# droneHAT.net
KiCad netlist of a schematic drawn in EAGLE
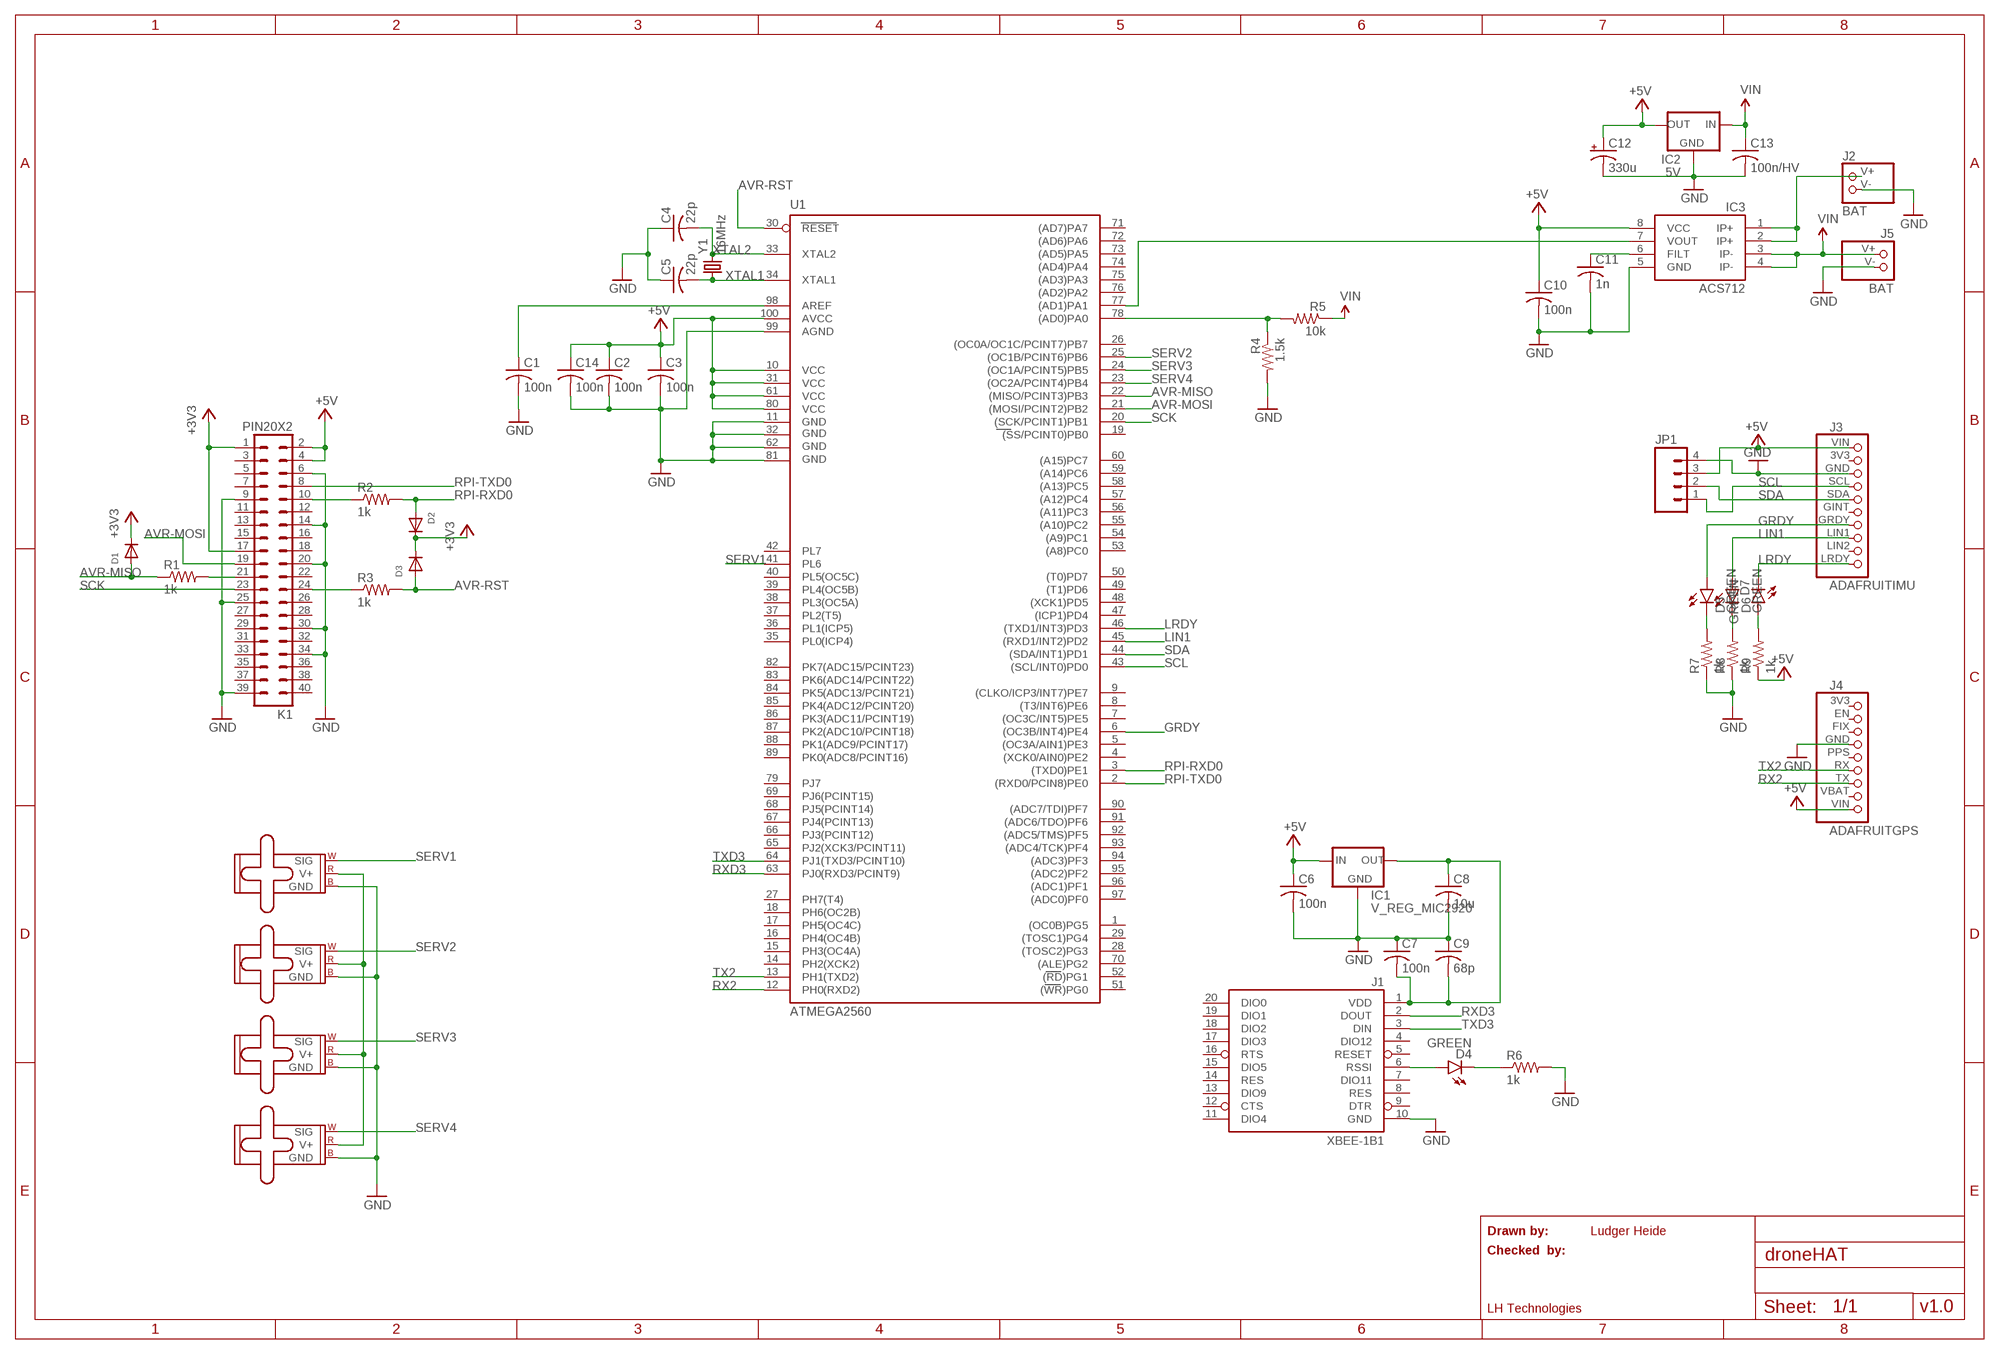
[diagram p0: schematic, sheet 1]

(export (version "E")
  (design (tool "Eeschema 10.0.6"))
  (components
    (comp (ref "C1")
      (value "100n")
      (footprint "eagle-import:C1206")
      (libsource (lib "eagle-import") (part "C-USC1206"))
    )
    (comp (ref "C2")
      (value "100n")
      (footprint "eagle-import:C1206")
      (libsource (lib "eagle-import") (part "C-USC1206"))
    )
    (comp (ref "C3")
      (value "100n")
      (footprint "eagle-import:C1206")
      (libsource (lib "eagle-import") (part "C-USC1206"))
    )
    (comp (ref "C4")
      (value "22p")
      (footprint "eagle-import:C1206")
      (libsource (lib "eagle-import") (part "C-USC1206"))
    )
    (comp (ref "C5")
      (value "22p")
      (footprint "eagle-import:C1206")
      (libsource (lib "eagle-import") (part "C-USC1206"))
    )
    (comp (ref "C6")
      (value "100n")
      (footprint "eagle-import:C1206")
      (libsource (lib "eagle-import") (part "C-USC1206"))
    )
    (comp (ref "C7")
      (value "100n")
      (footprint "eagle-import:C1206")
      (libsource (lib "eagle-import") (part "C-USC1206"))
    )
    (comp (ref "C8")
      (value "10u")
      (footprint "eagle-import:C1206")
      (libsource (lib "eagle-import") (part "C-USC1206"))
    )
    (comp (ref "C9")
      (value "68p")
      (footprint "eagle-import:C1206")
      (libsource (lib "eagle-import") (part "C-USC1206"))
    )
    (comp (ref "C10")
      (value "100n")
      (footprint "eagle-import:C1206")
      (libsource (lib "eagle-import") (part "C-USC1206"))
    )
    (comp (ref "C11")
      (value "1n")
      (footprint "eagle-import:C1206")
      (libsource (lib "eagle-import") (part "C-USC1206"))
    )
    (comp (ref "C12")
      (value "330u")
      (footprint "eagle-import:CPOL-RADIAL-100UF-25V")
      (libsource (lib "eagle-import") (part "CAP_POLPTH1"))
    )
    (comp (ref "C13")
      (value "100n/HV")
      (footprint "eagle-import:C1206")
      (libsource (lib "eagle-import") (part "C-USC1206"))
    )
    (comp (ref "C14")
      (value "100n")
      (footprint "eagle-import:C1206")
      (libsource (lib "eagle-import") (part "C-USC1206"))
    )
    (comp (ref "D1")
      (value "DIODEDO-1N4148")
      (footprint "eagle-import:DO-1N4148")
      (libsource (lib "eagle-import") (part "DIODEDO-1N4148"))
    )
    (comp (ref "D2")
      (value "DIODEDO-1N4148")
      (footprint "eagle-import:DO-1N4148")
      (libsource (lib "eagle-import") (part "DIODEDO-1N4148"))
    )
    (comp (ref "D3")
      (value "DIODEDO-1N4148")
      (footprint "eagle-import:DO-1N4148")
      (libsource (lib "eagle-import") (part "DIODEDO-1N4148"))
    )
    (comp (ref "D4")
      (value "GREEN")
      (footprint "eagle-import:LED-1206")
      (libsource (lib "eagle-import") (part "LED-GREENLARGE"))
    )
    (comp (ref "D5")
      (value "GREEN")
      (footprint "eagle-import:LED-1206")
      (libsource (lib "eagle-import") (part "LED-GREENLARGE"))
    )
    (comp (ref "D6")
      (value "GREEN")
      (footprint "eagle-import:LED-1206")
      (libsource (lib "eagle-import") (part "LED-GREENLARGE"))
    )
    (comp (ref "D7")
      (value "GREEN")
      (footprint "eagle-import:LED-1206")
      (libsource (lib "eagle-import") (part "LED-GREENLARGE"))
    )
    (comp (ref "IC1")
      (value "V_REG_MIC2920")
      (footprint "eagle-import:SOT223")
      (libsource (lib "eagle-import") (part "V_REG_MIC2920"))
    )
    (comp (ref "IC2")
      (value "5V")
      (footprint "eagle-import:TSRN1")
      (libsource (lib "eagle-import") (part "V_REG_78XX"))
    )
    (comp (ref "IC3")
      (value "ACS712")
      (footprint "eagle-import:SO08")
      (libsource (lib "eagle-import") (part "ACS712"))
    )
    (comp (ref "J1")
      (value "XBEE-1B1")
      (footprint "eagle-import:XBEE-1")
      (libsource (lib "eagle-import") (part "XBEE-1B1"))
    )
    (comp (ref "J2")
      (value "BAT")
      (footprint "eagle-import:BAT_HDR")
      (libsource (lib "eagle-import") (part "BAT"))
    )
    (comp (ref "J3")
      (value "ADAFRUITIMU")
      (footprint "eagle-import:ADAIMU")
      (libsource (lib "eagle-import") (part "ADAFRUITIMU"))
    )
    (comp (ref "J4")
      (value "ADAFRUITGPS")
      (footprint "eagle-import:ADAGPS")
      (libsource (lib "eagle-import") (part "ADAFRUITGPS"))
    )
    (comp (ref "J5")
      (value "BAT")
      (footprint "eagle-import:BAT_HDR")
      (libsource (lib "eagle-import") (part "BAT"))
    )
    (comp (ref "JP1")
      (value "M04PTH")
      (footprint "eagle-import:1X04")
      (libsource (lib "eagle-import") (part "M04PTH"))
    )
    (comp (ref "K1")
      (value "PIN20X2")
      (footprint "eagle-import:PIN_20X2")
      (libsource (lib "eagle-import") (part "PIN20X2"))
    )
    (comp (ref "M1")
      (value "SMALL_SERVO")
      (footprint "eagle-import:1X03")
      (libsource (lib "eagle-import") (part "SMALL_SERVO"))
    )
    (comp (ref "M2")
      (value "SMALL_SERVO")
      (footprint "eagle-import:1X03")
      (libsource (lib "eagle-import") (part "SMALL_SERVO"))
    )
    (comp (ref "M3")
      (value "SMALL_SERVO")
      (footprint "eagle-import:1X03")
      (libsource (lib "eagle-import") (part "SMALL_SERVO"))
    )
    (comp (ref "M4")
      (value "SMALL_SERVO")
      (footprint "eagle-import:1X03")
      (libsource (lib "eagle-import") (part "SMALL_SERVO"))
    )
    (comp (ref "R1")
      (value "1k")
      (footprint "eagle-import:M1206")
      (libsource (lib "eagle-import") (part "R-US_M1206"))
    )
    (comp (ref "R2")
      (value "1k")
      (footprint "eagle-import:M1206")
      (libsource (lib "eagle-import") (part "R-US_M1206"))
    )
    (comp (ref "R3")
      (value "1k")
      (footprint "eagle-import:M1206")
      (libsource (lib "eagle-import") (part "R-US_M1206"))
    )
    (comp (ref "R4")
      (value "1.5k")
      (footprint "eagle-import:M1206")
      (libsource (lib "eagle-import") (part "R-US_M1206"))
    )
    (comp (ref "R5")
      (value "10k")
      (footprint "eagle-import:M1206")
      (libsource (lib "eagle-import") (part "R-US_M1206"))
    )
    (comp (ref "R6")
      (value "1k")
      (footprint "eagle-import:M1206")
      (libsource (lib "eagle-import") (part "R-US_M1206"))
    )
    (comp (ref "R7")
      (value "1k")
      (footprint "eagle-import:M1206")
      (libsource (lib "eagle-import") (part "R-US_M1206"))
    )
    (comp (ref "R8")
      (value "1k")
      (footprint "eagle-import:M1206")
      (libsource (lib "eagle-import") (part "R-US_M1206"))
    )
    (comp (ref "R9")
      (value "1k")
      (footprint "eagle-import:M1206")
      (libsource (lib "eagle-import") (part "R-US_M1206"))
    )
    (comp (ref "U1")
      (value "ATMEGA2560")
      (footprint "eagle-import:TQFP100-LONG")
      (libsource (lib "eagle-import") (part "ATMEGA2560"))
    )
    (comp (ref "Y1")
      (value "16MHz")
      (footprint "eagle-import:HC49US")
      (libsource (lib "eagle-import") (part "CRYSTALHC49US"))
    )
  )
  (nets
    (net (code "1") (name "+3V3") (class "Default")
      (node (ref "D1") (pin "C") (pinfunction "C_C") (pintype "passive"))
      (node (ref "D2") (pin "C") (pinfunction "C_C") (pintype "passive"))
      (node (ref "D3") (pin "C") (pinfunction "C_C") (pintype "passive"))
      (node (ref "K1") (pin "1") (pinfunction "1_1") (pintype "passive"))
      (node (ref "K1") (pin "17") (pinfunction "17_17") (pintype "passive"))
    )
    (net (code "2") (name "+5V") (class "Default")
      (node (ref "C10") (pin "1") (pinfunction "1_1") (pintype "passive"))
      (node (ref "C12") (pin "1") (pinfunction "+_1") (pintype "passive"))
      (node (ref "C14") (pin "1") (pinfunction "1_1") (pintype "passive"))
      (node (ref "C2") (pin "1") (pinfunction "1_1") (pintype "passive"))
      (node (ref "C3") (pin "1") (pinfunction "1_1") (pintype "passive"))
      (node (ref "C6") (pin "1") (pinfunction "1_1") (pintype "passive"))
      (node (ref "IC1") (pin "1") (pinfunction "IN_1") (pintype "input"))
      (node (ref "IC2") (pin "3") (pinfunction "OUT_3") (pintype "output"))
      (node (ref "IC3") (pin "8") (pinfunction "VCC_8") (pintype "bidirectional"))
      (node (ref "J3") (pin "VIN") (pinfunction "1_VIN") (pintype "passive"))
      (node (ref "J4") (pin "VIN") (pinfunction "9_VIN") (pintype "passive"))
      (node (ref "JP1") (pin "3") (pinfunction "3_3") (pintype "passive"))
      (node (ref "K1") (pin "2") (pinfunction "2_2") (pintype "passive"))
      (node (ref "K1") (pin "4") (pinfunction "4_4") (pintype "passive"))
      (node (ref "R9") (pin "1") (pinfunction "1_1") (pintype "passive"))
      (node (ref "U1") (pin "10") (pinfunction "VCC_10") (pintype "power_in"))
      (node (ref "U1") (pin "100") (pinfunction "AVCC_100") (pintype "power_in"))
      (node (ref "U1") (pin "31") (pinfunction "VCC1_31") (pintype "power_in"))
      (node (ref "U1") (pin "61") (pinfunction "VCC2_61") (pintype "power_in"))
      (node (ref "U1") (pin "80") (pinfunction "VCC3_80") (pintype "power_in"))
    )
    (net (code "3") (name "/AVR-MISO") (class "Default")
      (node (ref "D1") (pin "A") (pinfunction "A_A") (pintype "passive"))
      (node (ref "R1") (pin "1") (pinfunction "1_1") (pintype "passive"))
      (node (ref "U1") (pin "22") (pinfunction "(MISO/PCINT3)PB3_22") (pintype "bidirectional"))
    )
    (net (code "4") (name "/AVR-MOSI") (class "Default")
      (node (ref "K1") (pin "19") (pinfunction "19_19") (pintype "passive"))
      (node (ref "U1") (pin "21") (pinfunction "(MOSI/PCINT2)PB2_21") (pintype "bidirectional"))
    )
    (net (code "5") (name "/AVR-RST") (class "Default")
      (node (ref "D3") (pin "A") (pinfunction "A_A") (pintype "passive"))
      (node (ref "R3") (pin "2") (pinfunction "2_2") (pintype "passive"))
      (node (ref "U1") (pin "30") (pinfunction "RESET_30") (pintype "input"))
    )
    (net (code "6") (name "/GRDY") (class "Default")
      (node (ref "D5") (pin "A") (pinfunction "A_A") (pintype "passive"))
      (node (ref "J3") (pin "GRDY") (pinfunction "7_GRDY") (pintype "passive"))
      (node (ref "U1") (pin "6") (pinfunction "(OC3B/INT4)PE4_6") (pintype "bidirectional"))
    )
    (net (code "7") (name "/LIN1") (class "Default")
      (node (ref "D6") (pin "A") (pinfunction "A_A") (pintype "passive"))
      (node (ref "J3") (pin "LIN1") (pinfunction "8_LIN1") (pintype "passive"))
      (node (ref "U1") (pin "45") (pinfunction "(RXD1/INT2)PD2_45") (pintype "bidirectional"))
    )
    (net (code "8") (name "/LRDY") (class "Default")
      (node (ref "D7") (pin "C") (pinfunction "C_C") (pintype "passive"))
      (node (ref "J3") (pin "LRDY") (pinfunction "10_LRDY") (pintype "passive"))
      (node (ref "U1") (pin "46") (pinfunction "(TXD1/INT3)PD3_46") (pintype "bidirectional"))
    )
    (net (code "9") (name "/RPI-RXD0") (class "Default")
      (node (ref "D2") (pin "A") (pinfunction "A_A") (pintype "passive"))
      (node (ref "R2") (pin "2") (pinfunction "2_2") (pintype "passive"))
      (node (ref "U1") (pin "3") (pinfunction "(TXD0)PE1_3") (pintype "bidirectional"))
    )
    (net (code "10") (name "/RPI-TXD0") (class "Default")
      (node (ref "K1") (pin "8") (pinfunction "8_8") (pintype "passive"))
      (node (ref "U1") (pin "2") (pinfunction "(RXD0/PCIN8)PE0_2") (pintype "bidirectional"))
    )
    (net (code "11") (name "/RX2") (class "Default")
      (node (ref "J4") (pin "TX") (pinfunction "7_TX") (pintype "passive"))
      (node (ref "U1") (pin "12") (pinfunction "PH0(RXD2)_12") (pintype "bidirectional"))
    )
    (net (code "12") (name "/RXD3") (class "Default")
      (node (ref "J1") (pin "2") (pinfunction "DOUT_2") (pintype "output"))
      (node (ref "U1") (pin "63") (pinfunction "PJ0(RXD3/PCINT9)_63") (pintype "bidirectional"))
    )
    (net (code "13") (name "/SCK") (class "Default")
      (node (ref "K1") (pin "23") (pinfunction "23_23") (pintype "passive"))
      (node (ref "U1") (pin "20") (pinfunction "(SCK/PCINT1)PB1_20") (pintype "bidirectional"))
    )
    (net (code "14") (name "/SCL") (class "Default")
      (node (ref "J3") (pin "SCL") (pinfunction "4_SCL") (pintype "passive"))
      (node (ref "JP1") (pin "1") (pinfunction "1_1") (pintype "passive"))
      (node (ref "U1") (pin "43") (pinfunction "(SCL/INT0)PD0_43") (pintype "bidirectional"))
    )
    (net (code "15") (name "/SDA") (class "Default")
      (node (ref "J3") (pin "SDA") (pinfunction "5_SDA") (pintype "passive"))
      (node (ref "JP1") (pin "2") (pinfunction "2_2") (pintype "passive"))
      (node (ref "U1") (pin "44") (pinfunction "(SDA/INT1)PD1_44") (pintype "bidirectional"))
    )
    (net (code "16") (name "/SERV1") (class "Default")
      (node (ref "M1") (pin "1") (pinfunction "SIG_1") (pintype "bidirectional"))
      (node (ref "U1") (pin "41") (pinfunction "PL6_41") (pintype "bidirectional"))
    )
    (net (code "17") (name "/SERV2") (class "Default")
      (node (ref "M2") (pin "1") (pinfunction "SIG_1") (pintype "bidirectional"))
      (node (ref "U1") (pin "25") (pinfunction "(OC1B/PCINT6)PB6_25") (pintype "bidirectional"))
    )
    (net (code "18") (name "/SERV3") (class "Default")
      (node (ref "M3") (pin "1") (pinfunction "SIG_1") (pintype "bidirectional"))
      (node (ref "U1") (pin "24") (pinfunction "(OC1A/PCINT5)PB5_24") (pintype "bidirectional"))
    )
    (net (code "19") (name "/SERV4") (class "Default")
      (node (ref "M4") (pin "1") (pinfunction "SIG_1") (pintype "bidirectional"))
      (node (ref "U1") (pin "23") (pinfunction "(OC2A/PCINT4)PB4_23") (pintype "bidirectional"))
    )
    (net (code "20") (name "/TX2") (class "Default")
      (node (ref "J4") (pin "RX") (pinfunction "6_RX") (pintype "passive"))
      (node (ref "U1") (pin "13") (pinfunction "PH1(TXD2)_13") (pintype "bidirectional"))
    )
    (net (code "21") (name "/TXD3") (class "Default")
      (node (ref "J1") (pin "3") (pinfunction "DIN_3") (pintype "input"))
      (node (ref "U1") (pin "64") (pinfunction "PJ1(TXD3/PCINT10)_64") (pintype "bidirectional"))
    )
    (net (code "22") (name "/XTAL1") (class "Default")
      (node (ref "C5") (pin "2") (pinfunction "2_2") (pintype "passive"))
      (node (ref "U1") (pin "34") (pinfunction "XTAL1_34") (pintype "input"))
      (node (ref "Y1") (pin "1") (pinfunction "1_1") (pintype "passive"))
    )
    (net (code "23") (name "/XTAL2") (class "Default")
      (node (ref "C4") (pin "2") (pinfunction "2_2") (pintype "passive"))
      (node (ref "U1") (pin "33") (pinfunction "XTAL2_33") (pintype "output"))
      (node (ref "Y1") (pin "2") (pinfunction "2_2") (pintype "passive"))
    )
    (net (code "24") (name "GND") (class "Default")
      (node (ref "C1") (pin "2") (pinfunction "2_2") (pintype "passive"))
      (node (ref "C10") (pin "2") (pinfunction "2_2") (pintype "passive"))
      (node (ref "C11") (pin "2") (pinfunction "2_2") (pintype "passive"))
      (node (ref "C12") (pin "2") (pinfunction "-_2") (pintype "passive"))
      (node (ref "C13") (pin "2") (pinfunction "2_2") (pintype "passive"))
      (node (ref "C14") (pin "2") (pinfunction "2_2") (pintype "passive"))
      (node (ref "C2") (pin "2") (pinfunction "2_2") (pintype "passive"))
      (node (ref "C3") (pin "2") (pinfunction "2_2") (pintype "passive"))
      (node (ref "C4") (pin "1") (pinfunction "1_1") (pintype "passive"))
      (node (ref "C5") (pin "1") (pinfunction "1_1") (pintype "passive"))
      (node (ref "C6") (pin "2") (pinfunction "2_2") (pintype "passive"))
      (node (ref "C7") (pin "1") (pinfunction "1_1") (pintype "passive"))
      (node (ref "C8") (pin "2") (pinfunction "2_2") (pintype "passive"))
      (node (ref "C9") (pin "1") (pinfunction "1_1") (pintype "passive"))
      (node (ref "IC1") (pin "2") (pinfunction "GND_2") (pintype "input"))
      (node (ref "IC2") (pin "2") (pinfunction "GND_2") (pintype "input"))
      (node (ref "IC3") (pin "5") (pinfunction "GND_5") (pintype "bidirectional"))
      (node (ref "J1") (pin "10") (pinfunction "GND_10") (pintype "power_in"))
      (node (ref "J2") (pin "V-") (pinfunction "V-_V-") (pintype "passive"))
      (node (ref "J3") (pin "GND") (pinfunction "3_GND") (pintype "passive"))
      (node (ref "J4") (pin "GND") (pinfunction "4_GND") (pintype "passive"))
      (node (ref "J5") (pin "V-") (pinfunction "V-_V-") (pintype "passive"))
      (node (ref "JP1") (pin "4") (pinfunction "4_4") (pintype "passive"))
      (node (ref "K1") (pin "14") (pinfunction "14_14") (pintype "passive"))
      (node (ref "K1") (pin "20") (pinfunction "20_20") (pintype "passive"))
      (node (ref "K1") (pin "25") (pinfunction "25_25") (pintype "passive"))
      (node (ref "K1") (pin "30") (pinfunction "30_30") (pintype "passive"))
      (node (ref "K1") (pin "34") (pinfunction "34_34") (pintype "passive"))
      (node (ref "K1") (pin "39") (pinfunction "39_39") (pintype "passive"))
      (node (ref "K1") (pin "6") (pinfunction "6_6") (pintype "passive"))
      (node (ref "K1") (pin "9") (pinfunction "9_9") (pintype "passive"))
      (node (ref "M1") (pin "3") (pinfunction "GND_3") (pintype "bidirectional"))
      (node (ref "M2") (pin "3") (pinfunction "GND_3") (pintype "bidirectional"))
      (node (ref "M3") (pin "3") (pinfunction "GND_3") (pintype "bidirectional"))
      (node (ref "M4") (pin "3") (pinfunction "GND_3") (pintype "bidirectional"))
      (node (ref "R4") (pin "2") (pinfunction "2_2") (pintype "passive"))
      (node (ref "R6") (pin "2") (pinfunction "2_2") (pintype "passive"))
      (node (ref "R7") (pin "1") (pinfunction "1_1") (pintype "passive"))
      (node (ref "R8") (pin "1") (pinfunction "1_1") (pintype "passive"))
      (node (ref "U1") (pin "11") (pinfunction "GND_11") (pintype "power_in"))
      (node (ref "U1") (pin "32") (pinfunction "GND1_32") (pintype "power_in"))
      (node (ref "U1") (pin "62") (pinfunction "GND2_62") (pintype "power_in"))
      (node (ref "U1") (pin "81") (pinfunction "GND3_81") (pintype "power_in"))
      (node (ref "U1") (pin "99") (pinfunction "AGND_99") (pintype "power_in"))
    )
    (net (code "25") (name "Net-(D4-PadC)") (class "Default")
      (node (ref "D4") (pin "C") (pinfunction "C_C") (pintype "passive"))
      (node (ref "R6") (pin "1") (pinfunction "1_1") (pintype "passive"))
    )
    (net (code "26") (name "Net-(D5-PadC)") (class "Default")
      (node (ref "D5") (pin "C") (pinfunction "C_C") (pintype "passive"))
      (node (ref "R7") (pin "2") (pinfunction "2_2") (pintype "passive"))
    )
    (net (code "27") (name "Net-(D6-PadC)") (class "Default")
      (node (ref "D6") (pin "C") (pinfunction "C_C") (pintype "passive"))
      (node (ref "R8") (pin "2") (pinfunction "2_2") (pintype "passive"))
    )
    (net (code "28") (name "Net-(D7-PadA)") (class "Default")
      (node (ref "D7") (pin "A") (pinfunction "A_A") (pintype "passive"))
      (node (ref "R9") (pin "2") (pinfunction "2_2") (pintype "passive"))
    )
    (net (code "29") (name "Net-(IC1-OUT)") (class "Default")
      (node (ref "C7") (pin "2") (pinfunction "2_2") (pintype "passive"))
      (node (ref "C8") (pin "1") (pinfunction "1_1") (pintype "passive"))
      (node (ref "C9") (pin "2") (pinfunction "2_2") (pintype "passive"))
      (node (ref "IC1") (pin "3") (pinfunction "OUT_3") (pintype "output"))
      (node (ref "J1") (pin "1") (pinfunction "VDD_1") (pintype "power_in"))
    )
    (net (code "30") (name "Net-(IC3-FILT)") (class "Default")
      (node (ref "C11") (pin "1") (pinfunction "1_1") (pintype "passive"))
      (node (ref "IC3") (pin "6") (pinfunction "FILT_6") (pintype "bidirectional"))
    )
    (net (code "31") (name "Net-(IC3-IP+-Pad1)") (class "Default")
      (node (ref "IC3") (pin "1") (pinfunction "IP+_1") (pintype "bidirectional"))
      (node (ref "IC3") (pin "2") (pinfunction "IP+_2") (pintype "bidirectional"))
      (node (ref "J2") (pin "V+") (pinfunction "V+_V+") (pintype "passive"))
    )
    (net (code "32") (name "Net-(IC3-VOUT)") (class "Default")
      (node (ref "IC3") (pin "7") (pinfunction "VOUT_7") (pintype "bidirectional"))
      (node (ref "U1") (pin "77") (pinfunction "(AD1)PA1_77") (pintype "bidirectional"))
    )
    (net (code "33") (name "Net-(J1-RSSI)") (class "Default")
      (node (ref "D4") (pin "A") (pinfunction "A_A") (pintype "passive"))
      (node (ref "J1") (pin "6") (pinfunction "RSSI_6") (pintype "bidirectional"))
    )
    (net (code "34") (name "Net-(K1-Pad10)") (class "Default")
      (node (ref "K1") (pin "10") (pinfunction "10_10") (pintype "passive"))
      (node (ref "R2") (pin "1") (pinfunction "1_1") (pintype "passive"))
    )
    (net (code "35") (name "Net-(K1-Pad21)") (class "Default")
      (node (ref "K1") (pin "21") (pinfunction "21_21") (pintype "passive"))
      (node (ref "R1") (pin "2") (pinfunction "2_2") (pintype "passive"))
    )
    (net (code "36") (name "Net-(K1-Pad24)") (class "Default")
      (node (ref "K1") (pin "24") (pinfunction "24_24") (pintype "passive"))
      (node (ref "R3") (pin "1") (pinfunction "1_1") (pintype "passive"))
    )
    (net (code "37") (name "Net-(M1-V+)") (class "Default")
      (node (ref "M1") (pin "2") (pinfunction "V+_2") (pintype "bidirectional"))
      (node (ref "M2") (pin "2") (pinfunction "V+_2") (pintype "bidirectional"))
      (node (ref "M3") (pin "2") (pinfunction "V+_2") (pintype "bidirectional"))
      (node (ref "M4") (pin "2") (pinfunction "V+_2") (pintype "bidirectional"))
    )
    (net (code "38") (name "Net-(U1-(AD0)PA0)") (class "Default")
      (node (ref "R4") (pin "1") (pinfunction "1_1") (pintype "passive"))
      (node (ref "R5") (pin "2") (pinfunction "2_2") (pintype "passive"))
      (node (ref "U1") (pin "78") (pinfunction "(AD0)PA0_78") (pintype "bidirectional"))
    )
    (net (code "39") (name "Net-(U1-AREF)") (class "Default")
      (node (ref "C1") (pin "1") (pinfunction "1_1") (pintype "passive"))
      (node (ref "U1") (pin "98") (pinfunction "AREF_98") (pintype "bidirectional"))
    )
    (net (code "40") (name "VIN") (class "Default")
      (node (ref "C13") (pin "1") (pinfunction "1_1") (pintype "passive"))
      (node (ref "IC2") (pin "1") (pinfunction "IN_1") (pintype "input"))
      (node (ref "IC3") (pin "3") (pinfunction "IP-_3") (pintype "bidirectional"))
      (node (ref "IC3") (pin "4") (pinfunction "IP-_4") (pintype "bidirectional"))
      (node (ref "J5") (pin "V+") (pinfunction "V+_V+") (pintype "passive"))
      (node (ref "R5") (pin "1") (pinfunction "1_1") (pintype "passive"))
    )
    (net (code "41") (name "unconnected-(J1-CTS-Pad12)") (class "Default")
      (node (ref "J1") (pin "12") (pinfunction "CTS_12") (pintype "output"))
    )
    (net (code "42") (name "unconnected-(J1-DIO0-Pad20)") (class "Default")
      (node (ref "J1") (pin "20") (pinfunction "DIO0_20") (pintype "bidirectional"))
    )
    (net (code "43") (name "unconnected-(J1-DIO1-Pad19)") (class "Default")
      (node (ref "J1") (pin "19") (pinfunction "DIO1_19") (pintype "bidirectional"))
    )
    (net (code "44") (name "unconnected-(J1-DIO2-Pad18)") (class "Default")
      (node (ref "J1") (pin "18") (pinfunction "DIO2_18") (pintype "bidirectional"))
    )
    (net (code "45") (name "unconnected-(J1-DIO3-Pad17)") (class "Default")
      (node (ref "J1") (pin "17") (pinfunction "DIO3_17") (pintype "bidirectional"))
    )
    (net (code "46") (name "unconnected-(J1-DIO4-Pad11)") (class "Default")
      (node (ref "J1") (pin "11") (pinfunction "DIO4_11") (pintype "bidirectional"))
    )
    (net (code "47") (name "unconnected-(J1-DIO5-Pad15)") (class "Default")
      (node (ref "J1") (pin "15") (pinfunction "DIO5_15") (pintype "bidirectional"))
    )
    (net (code "48") (name "unconnected-(J1-DIO9-Pad13)") (class "Default")
      (node (ref "J1") (pin "13") (pinfunction "DIO9_13") (pintype "bidirectional"))
    )
    (net (code "49") (name "unconnected-(J1-DIO11-Pad7)") (class "Default")
      (node (ref "J1") (pin "7") (pinfunction "DIO11_7") (pintype "bidirectional"))
    )
    (net (code "50") (name "unconnected-(J1-DIO12-Pad4)") (class "Default")
      (node (ref "J1") (pin "4") (pinfunction "DIO12_4") (pintype "bidirectional"))
    )
    (net (code "51") (name "unconnected-(J1-DTR-Pad9)") (class "Default")
      (node (ref "J1") (pin "9") (pinfunction "DTR_9") (pintype "bidirectional"))
    )
    (net (code "52") (name "unconnected-(J1-RES-Pad8)") (class "Default")
      (node (ref "J1") (pin "8") (pinfunction "RES_8") (pintype "bidirectional"))
    )
    (net (code "53") (name "unconnected-(J1-RES-Pad14)") (class "Default")
      (node (ref "J1") (pin "14") (pinfunction "RES_14") (pintype "bidirectional"))
    )
    (net (code "54") (name "unconnected-(J1-RESET-Pad5)") (class "Default")
      (node (ref "J1") (pin "5") (pinfunction "RESET_5") (pintype "input"))
    )
    (net (code "55") (name "unconnected-(J1-RTS-Pad16)") (class "Default")
      (node (ref "J1") (pin "16") (pinfunction "RTS_16") (pintype "input"))
    )
    (net (code "56") (name "unconnected-(J3-2-Pad3V3)") (class "Default")
      (node (ref "J3") (pin "3V3") (pinfunction "2_3V3") (pintype "passive"))
    )
    (net (code "57") (name "unconnected-(J3-6-PadGINT)") (class "Default")
      (node (ref "J3") (pin "GINT") (pinfunction "6_GINT") (pintype "passive"))
    )
    (net (code "58") (name "unconnected-(J3-9-PadLIN2)") (class "Default")
      (node (ref "J3") (pin "LIN2") (pinfunction "9_LIN2") (pintype "passive"))
    )
    (net (code "59") (name "unconnected-(J4-1-Pad3V3)") (class "Default")
      (node (ref "J4") (pin "3V3") (pinfunction "1_3V3") (pintype "passive"))
    )
    (net (code "60") (name "unconnected-(J4-2-PadEN)") (class "Default")
      (node (ref "J4") (pin "EN") (pinfunction "2_EN") (pintype "passive"))
    )
    (net (code "61") (name "unconnected-(J4-3-PadFIX)") (class "Default")
      (node (ref "J4") (pin "FIX") (pinfunction "3_FIX") (pintype "passive"))
    )
    (net (code "62") (name "unconnected-(J4-5-PadPPS)") (class "Default")
      (node (ref "J4") (pin "PPS") (pinfunction "5_PPS") (pintype "passive"))
    )
    (net (code "63") (name "unconnected-(J4-8-PadVBAT)") (class "Default")
      (node (ref "J4") (pin "VBAT") (pinfunction "8_VBAT") (pintype "passive"))
    )
    (net (code "64") (name "unconnected-(K1-Pad3)") (class "Default")
      (node (ref "K1") (pin "3") (pinfunction "3_3") (pintype "passive"))
    )
    (net (code "65") (name "unconnected-(K1-Pad5)") (class "Default")
      (node (ref "K1") (pin "5") (pinfunction "5_5") (pintype "passive"))
    )
    (net (code "66") (name "unconnected-(K1-Pad7)") (class "Default")
      (node (ref "K1") (pin "7") (pinfunction "7_7") (pintype "passive"))
    )
    (net (code "67") (name "unconnected-(K1-Pad11)") (class "Default")
      (node (ref "K1") (pin "11") (pinfunction "11_11") (pintype "passive"))
    )
    (net (code "68") (name "unconnected-(K1-Pad12)") (class "Default")
      (node (ref "K1") (pin "12") (pinfunction "12_12") (pintype "passive"))
    )
    (net (code "69") (name "unconnected-(K1-Pad13)") (class "Default")
      (node (ref "K1") (pin "13") (pinfunction "13_13") (pintype "passive"))
    )
    (net (code "70") (name "unconnected-(K1-Pad15)") (class "Default")
      (node (ref "K1") (pin "15") (pinfunction "15_15") (pintype "passive"))
    )
    (net (code "71") (name "unconnected-(K1-Pad16)") (class "Default")
      (node (ref "K1") (pin "16") (pinfunction "16_16") (pintype "passive"))
    )
    (net (code "72") (name "unconnected-(K1-Pad18)") (class "Default")
      (node (ref "K1") (pin "18") (pinfunction "18_18") (pintype "passive"))
    )
    (net (code "73") (name "unconnected-(K1-Pad22)") (class "Default")
      (node (ref "K1") (pin "22") (pinfunction "22_22") (pintype "passive"))
    )
    (net (code "74") (name "unconnected-(K1-Pad26)") (class "Default")
      (node (ref "K1") (pin "26") (pinfunction "26_26") (pintype "passive"))
    )
    (net (code "75") (name "unconnected-(K1-Pad27)") (class "Default")
      (node (ref "K1") (pin "27") (pinfunction "27_27") (pintype "passive"))
    )
    (net (code "76") (name "unconnected-(K1-Pad28)") (class "Default")
      (node (ref "K1") (pin "28") (pinfunction "28_28") (pintype "passive"))
    )
    (net (code "77") (name "unconnected-(K1-Pad29)") (class "Default")
      (node (ref "K1") (pin "29") (pinfunction "29_29") (pintype "passive"))
    )
    (net (code "78") (name "unconnected-(K1-Pad31)") (class "Default")
      (node (ref "K1") (pin "31") (pinfunction "31_31") (pintype "passive"))
    )
    (net (code "79") (name "unconnected-(K1-Pad32)") (class "Default")
      (node (ref "K1") (pin "32") (pinfunction "32_32") (pintype "passive"))
    )
    (net (code "80") (name "unconnected-(K1-Pad33)") (class "Default")
      (node (ref "K1") (pin "33") (pinfunction "33_33") (pintype "passive"))
    )
    (net (code "81") (name "unconnected-(K1-Pad35)") (class "Default")
      (node (ref "K1") (pin "35") (pinfunction "35_35") (pintype "passive"))
    )
    (net (code "82") (name "unconnected-(K1-Pad36)") (class "Default")
      (node (ref "K1") (pin "36") (pinfunction "36_36") (pintype "passive"))
    )
    (net (code "83") (name "unconnected-(K1-Pad37)") (class "Default")
      (node (ref "K1") (pin "37") (pinfunction "37_37") (pintype "passive"))
    )
    (net (code "84") (name "unconnected-(K1-Pad38)") (class "Default")
      (node (ref "K1") (pin "38") (pinfunction "38_38") (pintype "passive"))
    )
    (net (code "85") (name "unconnected-(K1-Pad40)") (class "Default")
      (node (ref "K1") (pin "40") (pinfunction "40_40") (pintype "passive"))
    )
    (net (code "86") (name "unconnected-(U1-(A8)PC0-Pad53)") (class "Default")
      (node (ref "U1") (pin "53") (pinfunction "(A8)PC0_53") (pintype "bidirectional"))
    )
    (net (code "87") (name "unconnected-(U1-(A9)PC1-Pad54)") (class "Default")
      (node (ref "U1") (pin "54") (pinfunction "(A9)PC1_54") (pintype "bidirectional"))
    )
    (net (code "88") (name "unconnected-(U1-(A10)PC2-Pad55)") (class "Default")
      (node (ref "U1") (pin "55") (pinfunction "(A10)PC2_55") (pintype "bidirectional"))
    )
    (net (code "89") (name "unconnected-(U1-(A11)PC3-Pad56)") (class "Default")
      (node (ref "U1") (pin "56") (pinfunction "(A11)PC3_56") (pintype "bidirectional"))
    )
    (net (code "90") (name "unconnected-(U1-(A12)PC4-Pad57)") (class "Default")
      (node (ref "U1") (pin "57") (pinfunction "(A12)PC4_57") (pintype "bidirectional"))
    )
    (net (code "91") (name "unconnected-(U1-(A13)PC5-Pad58)") (class "Default")
      (node (ref "U1") (pin "58") (pinfunction "(A13)PC5_58") (pintype "bidirectional"))
    )
    (net (code "92") (name "unconnected-(U1-(A14)PC6-Pad59)") (class "Default")
      (node (ref "U1") (pin "59") (pinfunction "(A14)PC6_59") (pintype "bidirectional"))
    )
    (net (code "93") (name "unconnected-(U1-(A15)PC7-Pad60)") (class "Default")
      (node (ref "U1") (pin "60") (pinfunction "(A15)PC7_60") (pintype "bidirectional"))
    )
    (net (code "94") (name "unconnected-(U1-(AD2)PA2-Pad76)") (class "Default")
      (node (ref "U1") (pin "76") (pinfunction "(AD2)PA2_76") (pintype "bidirectional"))
    )
    (net (code "95") (name "unconnected-(U1-(AD3)PA3-Pad75)") (class "Default")
      (node (ref "U1") (pin "75") (pinfunction "(AD3)PA3_75") (pintype "bidirectional"))
    )
    (net (code "96") (name "unconnected-(U1-(AD4)PA4-Pad74)") (class "Default")
      (node (ref "U1") (pin "74") (pinfunction "(AD4)PA4_74") (pintype "bidirectional"))
    )
    (net (code "97") (name "unconnected-(U1-(AD5)PA5-Pad73)") (class "Default")
      (node (ref "U1") (pin "73") (pinfunction "(AD5)PA5_73") (pintype "bidirectional"))
    )
    (net (code "98") (name "unconnected-(U1-(AD6)PA6-Pad72)") (class "Default")
      (node (ref "U1") (pin "72") (pinfunction "(AD6)PA6_72") (pintype "bidirectional"))
    )
    (net (code "99") (name "unconnected-(U1-(AD7)PA7-Pad71)") (class "Default")
      (node (ref "U1") (pin "71") (pinfunction "(AD7)PA7_71") (pintype "bidirectional"))
    )
    (net (code "100") (name "unconnected-(U1-(ADC0)PF0-Pad97)") (class "Default")
      (node (ref "U1") (pin "97") (pinfunction "(ADC0)PF0_97") (pintype "bidirectional"))
    )
    (net (code "101") (name "unconnected-(U1-(ADC1)PF1-Pad96)") (class "Default")
      (node (ref "U1") (pin "96") (pinfunction "(ADC1)PF1_96") (pintype "bidirectional"))
    )
    (net (code "102") (name "unconnected-(U1-(ADC2)PF2-Pad95)") (class "Default")
      (node (ref "U1") (pin "95") (pinfunction "(ADC2)PF2_95") (pintype "bidirectional"))
    )
    (net (code "103") (name "unconnected-(U1-(ADC3)PF3-Pad94)") (class "Default")
      (node (ref "U1") (pin "94") (pinfunction "(ADC3)PF3_94") (pintype "bidirectional"))
    )
    (net (code "104") (name "unconnected-(U1-(ADC4{slash}TCK)PF4-Pad93)") (class "Default")
      (node (ref "U1") (pin "93") (pinfunction "(ADC4/TCK)PF4_93") (pintype "bidirectional"))
    )
    (net (code "105") (name "unconnected-(U1-(ADC5{slash}TMS)PF5-Pad92)") (class "Default")
      (node (ref "U1") (pin "92") (pinfunction "(ADC5/TMS)PF5_92") (pintype "bidirectional"))
    )
    (net (code "106") (name "unconnected-(U1-(ADC6{slash}TDO)PF6-Pad91)") (class "Default")
      (node (ref "U1") (pin "91") (pinfunction "(ADC6/TDO)PF6_91") (pintype "bidirectional"))
    )
    (net (code "107") (name "unconnected-(U1-(ADC7{slash}TDI)PF7-Pad90)") (class "Default")
      (node (ref "U1") (pin "90") (pinfunction "(ADC7/TDI)PF7_90") (pintype "bidirectional"))
    )
    (net (code "108") (name "unconnected-(U1-(ALE)PG2-Pad70)") (class "Default")
      (node (ref "U1") (pin "70") (pinfunction "(ALE)PG2_70") (pintype "bidirectional"))
    )
    (net (code "109") (name "unconnected-(U1-(CLKO{slash}ICP3{slash}INT7)PE7-Pad9)") (class "Default")
      (node (ref "U1") (pin "9") (pinfunction "(CLKO/ICP3/INT7)PE7_9") (pintype "bidirectional"))
    )
    (net (code "110") (name "unconnected-(U1-(ICP1)PD4-Pad47)") (class "Default")
      (node (ref "U1") (pin "47") (pinfunction "(ICP1)PD4_47") (pintype "bidirectional"))
    )
    (net (code "111") (name "unconnected-(U1-(OC0A{slash}OC1C{slash}PCINT7)PB7-Pad26)") (class "Default")
      (node (ref "U1") (pin "26") (pinfunction "(OC0A/OC1C/PCINT7)PB7_26") (pintype "bidirectional"))
    )
    (net (code "112") (name "unconnected-(U1-(OC0B)PG5-Pad1)") (class "Default")
      (node (ref "U1") (pin "1") (pinfunction "(OC0B)PG5_1") (pintype "bidirectional"))
    )
    (net (code "113") (name "unconnected-(U1-(OC3A{slash}AIN1)PE3-Pad5)") (class "Default")
      (node (ref "U1") (pin "5") (pinfunction "(OC3A/AIN1)PE3_5") (pintype "bidirectional"))
    )
    (net (code "114") (name "unconnected-(U1-(OC3C{slash}INT5)PE5-Pad7)") (class "Default")
      (node (ref "U1") (pin "7") (pinfunction "(OC3C/INT5)PE5_7") (pintype "bidirectional"))
    )
    (net (code "115") (name "unconnected-(U1-(RD)PG1-Pad52)") (class "Default")
      (node (ref "U1") (pin "52") (pinfunction "(RD)PG1_52") (pintype "bidirectional"))
    )
    (net (code "116") (name "unconnected-(U1-(SS{slash}PCINT0)PB0-Pad19)") (class "Default")
      (node (ref "U1") (pin "19") (pinfunction "(SS/PCINT0)PB0_19") (pintype "bidirectional"))
    )
    (net (code "117") (name "unconnected-(U1-(T0)PD7-Pad50)") (class "Default")
      (node (ref "U1") (pin "50") (pinfunction "(T0)PD7_50") (pintype "bidirectional"))
    )
    (net (code "118") (name "unconnected-(U1-(T1)PD6-Pad49)") (class "Default")
      (node (ref "U1") (pin "49") (pinfunction "(T1)PD6_49") (pintype "bidirectional"))
    )
    (net (code "119") (name "unconnected-(U1-(T3{slash}INT6)PE6-Pad8)") (class "Default")
      (node (ref "U1") (pin "8") (pinfunction "(T3/INT6)PE6_8") (pintype "bidirectional"))
    )
    (net (code "120") (name "unconnected-(U1-(TOSC1)PG4-Pad29)") (class "Default")
      (node (ref "U1") (pin "29") (pinfunction "(TOSC1)PG4_29") (pintype "bidirectional"))
    )
    (net (code "121") (name "unconnected-(U1-(TOSC2)PG3-Pad28)") (class "Default")
      (node (ref "U1") (pin "28") (pinfunction "(TOSC2)PG3_28") (pintype "bidirectional"))
    )
    (net (code "122") (name "unconnected-(U1-(WR)PG0-Pad51)") (class "Default")
      (node (ref "U1") (pin "51") (pinfunction "(WR)PG0_51") (pintype "bidirectional"))
    )
    (net (code "123") (name "unconnected-(U1-(XCK0{slash}AIN0)PE2-Pad4)") (class "Default")
      (node (ref "U1") (pin "4") (pinfunction "(XCK0/AIN0)PE2_4") (pintype "bidirectional"))
    )
    (net (code "124") (name "unconnected-(U1-(XCK1)PD5-Pad48)") (class "Default")
      (node (ref "U1") (pin "48") (pinfunction "(XCK1)PD5_48") (pintype "bidirectional"))
    )
    (net (code "125") (name "unconnected-(U1-PH2(XCK2)-Pad14)") (class "Default")
      (node (ref "U1") (pin "14") (pinfunction "PH2(XCK2)_14") (pintype "bidirectional"))
    )
    (net (code "126") (name "unconnected-(U1-PH3(OC4A)-Pad15)") (class "Default")
      (node (ref "U1") (pin "15") (pinfunction "PH3(OC4A)_15") (pintype "bidirectional"))
    )
    (net (code "127") (name "unconnected-(U1-PH4(OC4B)-Pad16)") (class "Default")
      (node (ref "U1") (pin "16") (pinfunction "PH4(OC4B)_16") (pintype "bidirectional"))
    )
    (net (code "128") (name "unconnected-(U1-PH5(OC4C)-Pad17)") (class "Default")
      (node (ref "U1") (pin "17") (pinfunction "PH5(OC4C)_17") (pintype "bidirectional"))
    )
    (net (code "129") (name "unconnected-(U1-PH6(OC2B)-Pad18)") (class "Default")
      (node (ref "U1") (pin "18") (pinfunction "PH6(OC2B)_18") (pintype "bidirectional"))
    )
    (net (code "130") (name "unconnected-(U1-PH7(T4)-Pad27)") (class "Default")
      (node (ref "U1") (pin "27") (pinfunction "PH7(T4)_27") (pintype "bidirectional"))
    )
    (net (code "131") (name "unconnected-(U1-PJ2(XCK3{slash}PCINT11)-Pad65)") (class "Default")
      (node (ref "U1") (pin "65") (pinfunction "PJ2(XCK3/PCINT11)_65") (pintype "bidirectional"))
    )
    (net (code "132") (name "unconnected-(U1-PJ3(PCINT12)-Pad66)") (class "Default")
      (node (ref "U1") (pin "66") (pinfunction "PJ3(PCINT12)_66") (pintype "bidirectional"))
    )
    (net (code "133") (name "unconnected-(U1-PJ4(PCINT13)-Pad67)") (class "Default")
      (node (ref "U1") (pin "67") (pinfunction "PJ4(PCINT13)_67") (pintype "bidirectional"))
    )
    (net (code "134") (name "unconnected-(U1-PJ5(PCINT14)-Pad68)") (class "Default")
      (node (ref "U1") (pin "68") (pinfunction "PJ5(PCINT14)_68") (pintype "bidirectional"))
    )
    (net (code "135") (name "unconnected-(U1-PJ6(PCINT15)-Pad69)") (class "Default")
      (node (ref "U1") (pin "69") (pinfunction "PJ6(PCINT15)_69") (pintype "bidirectional"))
    )
    (net (code "136") (name "unconnected-(U1-PJ7-Pad79)") (class "Default")
      (node (ref "U1") (pin "79") (pinfunction "PJ7_79") (pintype "bidirectional"))
    )
    (net (code "137") (name "unconnected-(U1-PK0(ADC8{slash}PCINT16)-Pad89)") (class "Default")
      (node (ref "U1") (pin "89") (pinfunction "PK0(ADC8/PCINT16)_89") (pintype "bidirectional"))
    )
    (net (code "138") (name "unconnected-(U1-PK1(ADC9{slash}PCINT17)-Pad88)") (class "Default")
      (node (ref "U1") (pin "88") (pinfunction "PK1(ADC9/PCINT17)_88") (pintype "bidirectional"))
    )
    (net (code "139") (name "unconnected-(U1-PK2(ADC10{slash}PCINT18)-Pad87)") (class "Default")
      (node (ref "U1") (pin "87") (pinfunction "PK2(ADC10/PCINT18)_87") (pintype "bidirectional"))
    )
    (net (code "140") (name "unconnected-(U1-PK3(ADC11{slash}PCINT19)-Pad86)") (class "Default")
      (node (ref "U1") (pin "86") (pinfunction "PK3(ADC11/PCINT19)_86") (pintype "bidirectional"))
    )
    (net (code "141") (name "unconnected-(U1-PK4(ADC12{slash}PCINT20)-Pad85)") (class "Default")
      (node (ref "U1") (pin "85") (pinfunction "PK4(ADC12/PCINT20)_85") (pintype "bidirectional"))
    )
    (net (code "142") (name "unconnected-(U1-PK5(ADC13{slash}PCINT21)-Pad84)") (class "Default")
      (node (ref "U1") (pin "84") (pinfunction "PK5(ADC13/PCINT21)_84") (pintype "bidirectional"))
    )
    (net (code "143") (name "unconnected-(U1-PK6(ADC14{slash}PCINT22)-Pad83)") (class "Default")
      (node (ref "U1") (pin "83") (pinfunction "PK6(ADC14/PCINT22)_83") (pintype "bidirectional"))
    )
    (net (code "144") (name "unconnected-(U1-PK7(ADC15{slash}PCINT23)-Pad82)") (class "Default")
      (node (ref "U1") (pin "82") (pinfunction "PK7(ADC15/PCINT23)_82") (pintype "bidirectional"))
    )
    (net (code "145") (name "unconnected-(U1-PL0(ICP4)-Pad35)") (class "Default")
      (node (ref "U1") (pin "35") (pinfunction "PL0(ICP4)_35") (pintype "bidirectional"))
    )
    (net (code "146") (name "unconnected-(U1-PL1(ICP5)-Pad36)") (class "Default")
      (node (ref "U1") (pin "36") (pinfunction "PL1(ICP5)_36") (pintype "bidirectional"))
    )
    (net (code "147") (name "unconnected-(U1-PL2(T5)-Pad37)") (class "Default")
      (node (ref "U1") (pin "37") (pinfunction "PL2(T5)_37") (pintype "bidirectional"))
    )
    (net (code "148") (name "unconnected-(U1-PL3(OC5A)-Pad38)") (class "Default")
      (node (ref "U1") (pin "38") (pinfunction "PL3(OC5A)_38") (pintype "bidirectional"))
    )
    (net (code "149") (name "unconnected-(U1-PL4(OC5B)-Pad39)") (class "Default")
      (node (ref "U1") (pin "39") (pinfunction "PL4(OC5B)_39") (pintype "bidirectional"))
    )
    (net (code "150") (name "unconnected-(U1-PL5(OC5C)-Pad40)") (class "Default")
      (node (ref "U1") (pin "40") (pinfunction "PL5(OC5C)_40") (pintype "bidirectional"))
    )
    (net (code "151") (name "unconnected-(U1-PL7-Pad42)") (class "Default")
      (node (ref "U1") (pin "42") (pinfunction "PL7_42") (pintype "bidirectional"))
    )
  )
)
